# Power.net
KiCad netlist of a schematic drawn in Altium Designer
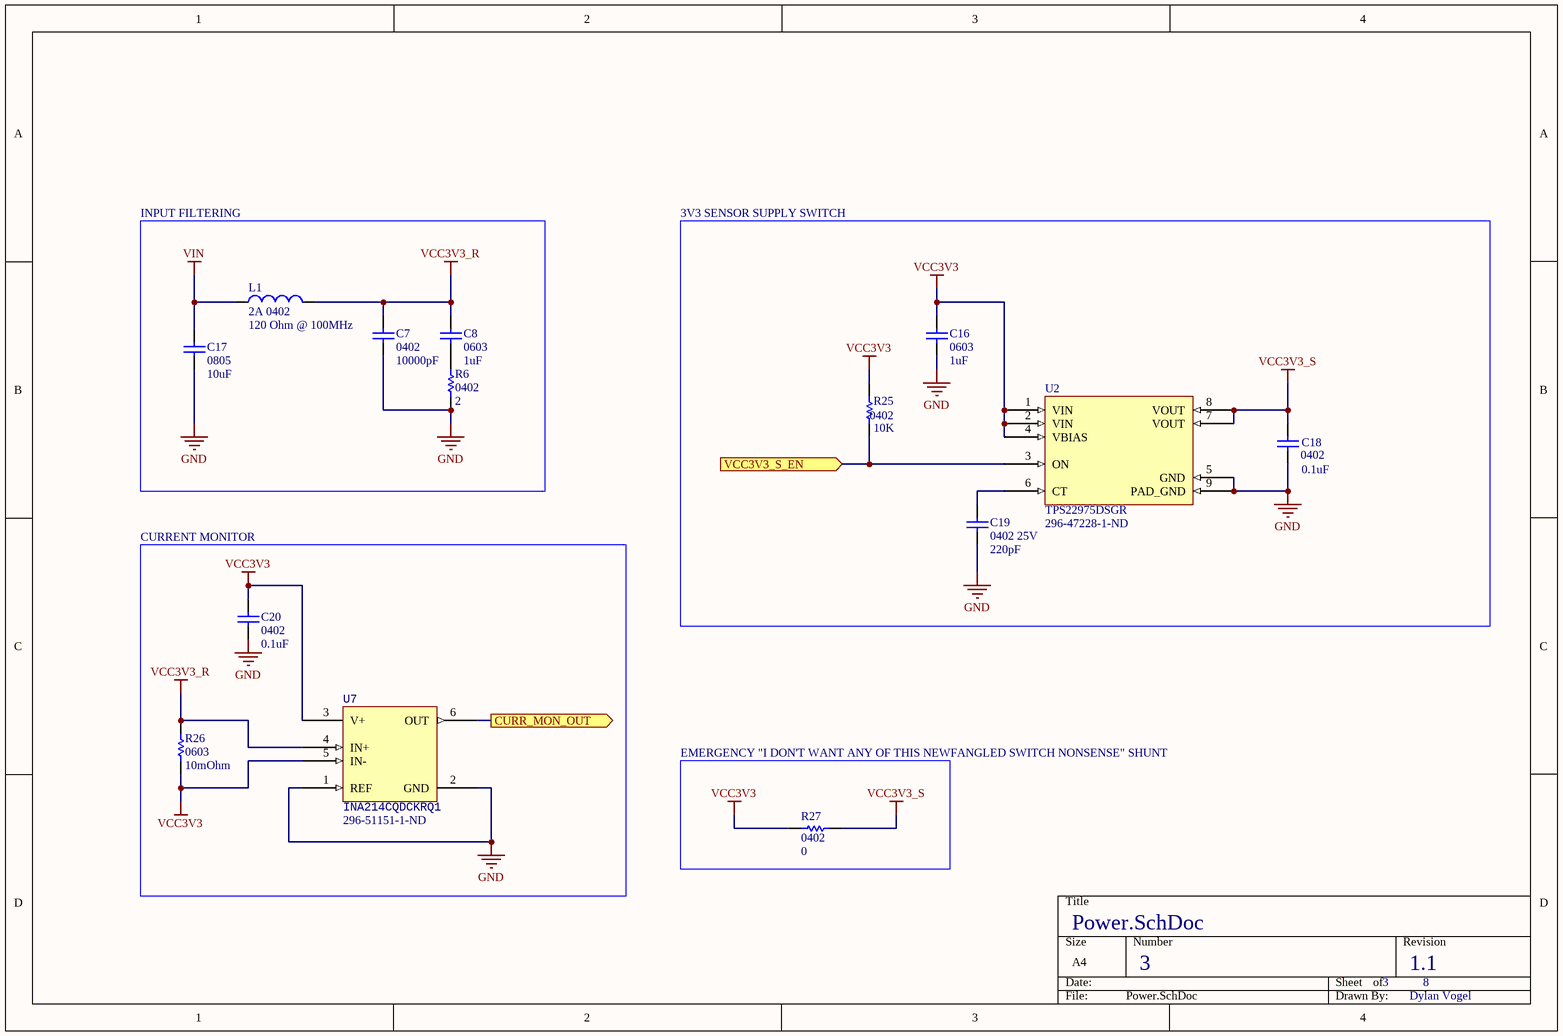
[diagram p0: Power.SchDoc]

(export (version "E")
  (design (tool "Eeschema 10.0.6"))
  (components
    (comp (ref "C7")
      (value "0402")
      (footprint "CAP0402R")
      (description "Capacitor")
      (fields (field (name "ALTIUM_VALUE") "10000pF") (field (name "PUBLISHER") "Altium Limited"))
      (libsource (lib "Miscellaneous Devices") (part "Cap"))
    )
    (comp (ref "C8")
      (value "0603")
      (footprint "CAP0603R")
      (description "Capacitor")
      (fields (field (name "ALTIUM_VALUE") "1uF") (field (name "PUBLISHER") "Altium Limited"))
      (libsource (lib "Miscellaneous Devices") (part "Cap"))
    )
    (comp (ref "C16")
      (value "0603")
      (footprint "CAP0603R")
      (description "Capacitor")
      (fields (field (name "ALTIUM_VALUE") "1uF") (field (name "PUBLISHER") "Altium Limited"))
      (libsource (lib "Miscellaneous Devices") (part "Cap"))
    )
    (comp (ref "C17")
      (value "0805")
      (footprint "CAP0805R")
      (description "Capacitor")
      (fields (field (name "ALTIUM_VALUE") "10uF") (field (name "PUBLISHER") "Altium Limited"))
      (libsource (lib "Miscellaneous Devices") (part "Cap"))
    )
    (comp (ref "C18")
      (value "0402")
      (footprint "CAP0402R")
      (description "Capacitor (Semiconductor SIM Model)")
      (fields
        (field (name "ALTIUM_VALUE") "0.1uF")
        (field (name "MANUFACTURER") "Murata")
        (field (name "MANUFACTURER PART NUMBER") "GCM155R71C104KA55J")
        (field (name "PUBLISHER") "Altium Limited")
      )
      (libsource (lib "Miscellaneous Devices") (part "Cap Semi"))
    )
    (comp (ref "C19")
      (value "0402 25V")
      (footprint "CAP0402R")
      (description "Capacitor")
      (fields
        (field (name "ALTIUM_VALUE") "220pF")
        (field (name "MANUFACTURER") "Murata")
        (field (name "MANUFACTURER PART NUMBER") "GCM155R71H221KA37D")
        (field (name "PUBLISHER") "Altium Limited")
      )
      (libsource (lib "Miscellaneous Devices") (part "Cap"))
    )
    (comp (ref "C20")
      (value "0402")
      (footprint "CAP0402R")
      (description "Capacitor")
      (fields (field (name "ALTIUM_VALUE") "0.1uF") (field (name "PUBLISHER") "Altium Limited"))
      (libsource (lib "Miscellaneous Devices") (part "Cap"))
    )
    (comp (ref "L1")
      (value "2A 0402")
      (footprint "RES0402R")
      (description "Inductor")
      (fields
        (field (name "ALTIUM_VALUE") "120 Ohm @ 100MHz")
        (field (name "MANUFACTURER") "Murata")
        (field (name "MANUFACTURER PART NUMBER") "BLM15PX121SZ1D")
        (field (name "PUBLISHER") "Altium Limited")
      )
      (libsource (lib "Miscellaneous Devices") (part "Inductor"))
    )
    (comp (ref "R6")
      (value "0402")
      (footprint "RES0402R")
      (description "Resistor")
      (fields (field (name "ALTIUM_VALUE") "2") (field (name "PUBLISHER") "Altium Limited"))
      (libsource (lib "Miscellaneous Devices") (part "Res1"))
    )
    (comp (ref "R25")
      (value "0402")
      (footprint "RES0402R")
      (description "Resistor")
      (fields (field (name "ALTIUM_VALUE") "10K") (field (name "PUBLISHER") "Altium Limited"))
      (libsource (lib "Miscellaneous Devices") (part "Res1"))
    )
    (comp (ref "R26")
      (value "0603")
      (footprint "RES0603R")
      (description "Resistor")
      (fields (field (name "ALTIUM_VALUE") "10mOhm") (field (name "PUBLISHER") "Altium Limited"))
      (libsource (lib "Miscellaneous Devices") (part "Res1"))
    )
    (comp (ref "R27")
      (value "0402")
      (footprint "RES0402R")
      (description "Resistor")
      (fields
        (field (name "ALTIUM_VALUE") "0")
        (field (name "MANUFACTURER") "Panasonic")
        (field (name "MANUFACTURER PART NUMBER") "ERJ2GE0R00X")
        (field (name "PUBLISHER") "Altium Limited")
      )
      (libsource (lib "Miscellaneous Devices") (part "Res1"))
    )
    (comp (ref "U2")
      (value "TPS22975DSGR")
      (footprint "DSG0008A")
      (description "IC LOAD SWITCH N-CH 6A 8WSON")
      (fields (field (name "SUPPLIER PART NUMBER 1") "296-47228-1-ND"))
      (libsource (lib "ICs") (part "TPS22975DSGR"))
    )
    (comp (ref "U7")
      (value "INA214CQDCKRQ1")
      (footprint "TI-SOT-SC70 (DCK)")
      (description "IC CURR SENSE 1 CIRCUIT SC70-6")
      (fields (field (name "SUPPLIER PART NUMBER 1") "296-51151-1-ND"))
      (libsource (lib "heron-general") (part "INA214CQDCKRQ1"))
    )
  )
  (nets
    (net (code "1") (name "/CURR_MON_OUT") (class "Default")
      (node (ref "U7") (pin "6") (pinfunction "OUT_6") (pintype "output"))
    )
    (net (code "2") (name "/VCC3V3_S_EN") (class "Default")
      (node (ref "R25") (pin "1") (pinfunction "1_1") (pintype "passive"))
      (node (ref "U2") (pin "3") (pinfunction "ON_3") (pintype "input"))
    )
    (net (code "3") (name "GND") (class "Default")
      (node (ref "C16") (pin "1") (pinfunction "1_1") (pintype "passive"))
      (node (ref "C17") (pin "1") (pinfunction "1_1") (pintype "passive"))
      (node (ref "C18") (pin "1") (pinfunction "1_1") (pintype "passive"))
      (node (ref "C19") (pin "1") (pinfunction "1_1") (pintype "passive"))
      (node (ref "C20") (pin "2") (pinfunction "2_2") (pintype "passive"))
      (node (ref "C7") (pin "1") (pinfunction "1_1") (pintype "passive"))
      (node (ref "R6") (pin "1") (pinfunction "1_1") (pintype "passive"))
      (node (ref "U2") (pin "5") (pinfunction "GND_5") (pintype "input"))
      (node (ref "U2") (pin "9") (pinfunction "PAD_GND_9") (pintype "input"))
      (node (ref "U7") (pin "1") (pinfunction "REF_1") (pintype "input"))
      (node (ref "U7") (pin "2") (pinfunction "GND_2") (pintype "power_in"))
    )
    (net (code "4") (name "Net-(C8-Pad1)") (class "Default")
      (node (ref "C8") (pin "1") (pinfunction "1_1") (pintype "passive"))
      (node (ref "R6") (pin "2") (pinfunction "2_2") (pintype "passive"))
    )
    (net (code "5") (name "Net-(U2-CT)") (class "Default")
      (node (ref "C19") (pin "2") (pinfunction "2_2") (pintype "passive"))
      (node (ref "U2") (pin "6") (pinfunction "CT_6") (pintype "input"))
    )
    (net (code "6") (name "VCC3V3") (class "Default")
      (node (ref "C16") (pin "2") (pinfunction "2_2") (pintype "passive"))
      (node (ref "C20") (pin "1") (pinfunction "1_1") (pintype "passive"))
      (node (ref "R25") (pin "2") (pinfunction "2_2") (pintype "passive"))
      (node (ref "R26") (pin "2") (pinfunction "2_2") (pintype "passive"))
      (node (ref "R27") (pin "2") (pinfunction "2_2") (pintype "passive"))
      (node (ref "U2") (pin "1") (pinfunction "VIN_1") (pintype "input"))
      (node (ref "U2") (pin "2") (pinfunction "VIN_2") (pintype "input"))
      (node (ref "U2") (pin "4") (pinfunction "VBIAS_4") (pintype "input"))
      (node (ref "U7") (pin "3") (pinfunction "V+_3") (pintype "power_in"))
      (node (ref "U7") (pin "5") (pinfunction "IN-_5") (pintype "input"))
    )
    (net (code "7") (name "VCC3V3_R") (class "Default")
      (node (ref "C7") (pin "2") (pinfunction "2_2") (pintype "passive"))
      (node (ref "C8") (pin "2") (pinfunction "2_2") (pintype "passive"))
      (node (ref "L1") (pin "2") (pinfunction "2_2") (pintype "passive"))
      (node (ref "R26") (pin "1") (pinfunction "1_1") (pintype "passive"))
      (node (ref "U7") (pin "4") (pinfunction "IN+_4") (pintype "input"))
    )
    (net (code "8") (name "VCC3V3_S") (class "Default")
      (node (ref "C18") (pin "2") (pinfunction "2_2") (pintype "passive"))
      (node (ref "R27") (pin "1") (pinfunction "1_1") (pintype "passive"))
      (node (ref "U2") (pin "7") (pinfunction "VOUT_7") (pintype "input"))
      (node (ref "U2") (pin "8") (pinfunction "VOUT_8") (pintype "input"))
    )
    (net (code "9") (name "VIN") (class "Default")
      (node (ref "C17") (pin "2") (pinfunction "2_2") (pintype "passive"))
      (node (ref "L1") (pin "1") (pinfunction "1_1") (pintype "passive"))
    )
  )
)
